# simrig_controller.net
KiCad netlist of a schematic drawn in Altium Designer
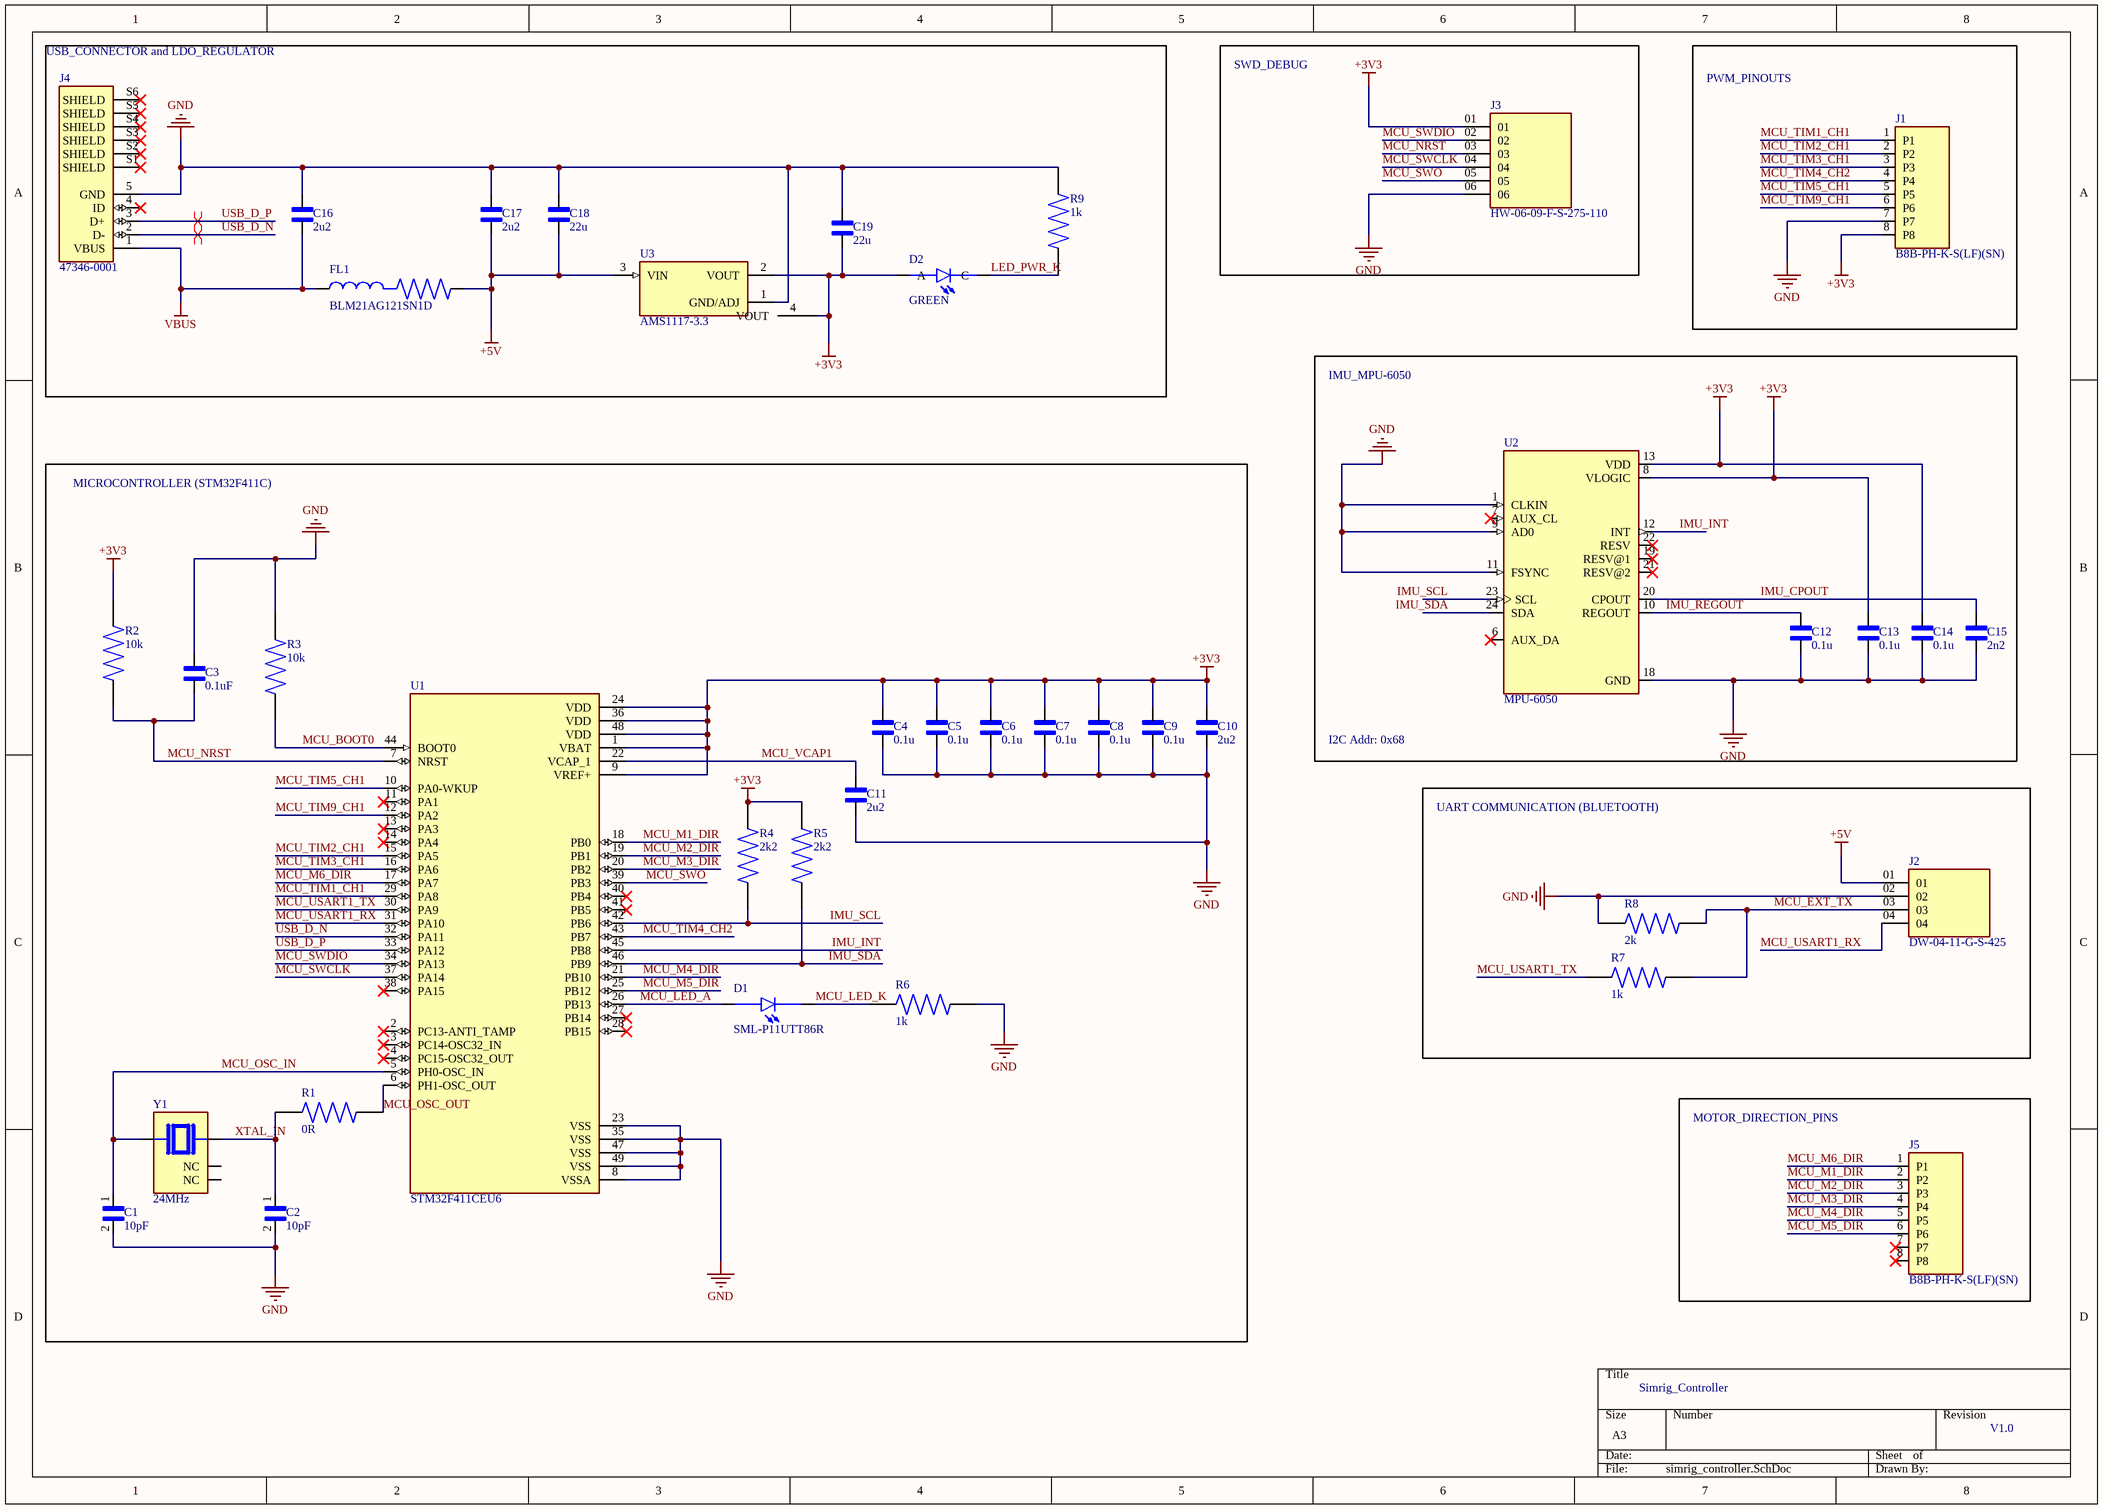
[diagram p0: simrig_controller.SchDoc]

(export (version "E")
  (design (tool "Eeschema 10.0.6"))
  (components
    (comp (ref "C1")
      (value "10pF")
      (footprint "CAPC1005X55N")
      (description "CERAMIC CAPACITOR 10PF 50V, C0G, 5%, 0402, FULL REEL")
      (fields (field (name "MF") "{'manufacturer': u'Yageo'}") (field (name "MP") "CC0402JRNPO9BN100"))
      (libsource (lib "SnapEDA_Library") (part "CC0402JRNPO9BN100"))
    )
    (comp (ref "C2")
      (value "10pF")
      (footprint "CAPC1005X55N")
      (description "CERAMIC CAPACITOR 10PF 50V, C0G, 5%, 0402, FULL REEL")
      (fields (field (name "MF") "{'manufacturer': u'Yageo'}") (field (name "MP") "CC0402JRNPO9BN100"))
      (libsource (lib "SnapEDA_Library") (part "CC0402JRNPO9BN100"))
    )
    (comp (ref "C3")
      (value "0.1uF")
      (footprint "CAPC1005X55N")
      (description "CAP CER 0.1UF 16V 10% X7R 0402")
      (fields (field (name "MF") "{'manufacturer': u'KEMET'}") (field (name "MP") "C0402C104K4RALTU"))
      (libsource (lib "SnapEDA_Library") (part "C0402C104K4RALTU"))
    )
    (comp (ref "C4")
      (value "0.1u")
      (footprint "CAPC1005X55N")
      (description "CAP CER 0.1UF 16V 10% X7R 0402")
      (fields (field (name "MF") "{'manufacturer': u'KEMET'}") (field (name "MP") "C0402C104K4RALTU"))
      (libsource (lib "SnapEDA_Library") (part "C0402C104K4RALTU"))
    )
    (comp (ref "C5")
      (value "0.1u")
      (footprint "CAPC1005X55N")
      (description "CAP CER 0.1UF 16V 10% X7R 0402")
      (fields (field (name "MF") "{'manufacturer': u'KEMET'}") (field (name "MP") "C0402C104K4RALTU"))
      (libsource (lib "SnapEDA_Library") (part "C0402C104K4RALTU"))
    )
    (comp (ref "C6")
      (value "0.1u")
      (footprint "CAPC1005X55N")
      (description "CAP CER 0.1UF 16V 10% X7R 0402")
      (fields (field (name "MF") "{'manufacturer': u'KEMET'}") (field (name "MP") "C0402C104K4RALTU"))
      (libsource (lib "SnapEDA_Library") (part "C0402C104K4RALTU"))
    )
    (comp (ref "C7")
      (value "0.1u")
      (footprint "CAPC1005X55N")
      (description "CAP CER 0.1UF 16V 10% X7R 0402")
      (fields (field (name "MF") "{'manufacturer': u'KEMET'}") (field (name "MP") "C0402C104K4RALTU"))
      (libsource (lib "SnapEDA_Library") (part "C0402C104K4RALTU"))
    )
    (comp (ref "C8")
      (value "0.1u")
      (footprint "CAPC1005X55N")
      (description "CAP CER 0.1UF 16V 10% X7R 0402")
      (fields (field (name "MF") "{'manufacturer': u'KEMET'}") (field (name "MP") "C0402C104K4RALTU"))
      (libsource (lib "SnapEDA_Library") (part "C0402C104K4RALTU"))
    )
    (comp (ref "C9")
      (value "0.1u")
      (footprint "CAPC1005X55N")
      (description "CAP CER 0.1UF 16V 10% X7R 0402")
      (fields (field (name "MF") "{'manufacturer': u'KEMET'}") (field (name "MP") "C0402C104K4RALTU"))
      (libsource (lib "SnapEDA_Library") (part "C0402C104K4RALTU"))
    )
    (comp (ref "C10")
      (value "2u2")
      (footprint "CAPC1608X90N")
      (fields (field (name "MF") "{'manufacturer': u'Murata'}") (field (name "MP") "GRM188R61E225MA12D"))
      (libsource (lib "SnapEDA_Library") (part "GRM188R61E225MA12D"))
    )
    (comp (ref "C11")
      (value "2u2")
      (footprint "CAPC1608X90N")
      (fields (field (name "MF") "{'manufacturer': u'Murata'}") (field (name "MP") "GRM188R61E225MA12D"))
      (libsource (lib "SnapEDA_Library") (part "GRM188R61E225MA12D"))
    )
    (comp (ref "C12")
      (value "0.1u")
      (footprint "CAPC1005X55N")
      (description "CAP CER 0.1UF 16V 10% X7R 0402")
      (fields (field (name "MF") "{'manufacturer': u'KEMET'}") (field (name "MP") "C0402C104K4RALTU"))
      (libsource (lib "") (part "C0402C104K4RALTU_1"))
    )
    (comp (ref "C13")
      (value "0.1u")
      (footprint "CAPC1005X55N")
      (description "CAP CER 0.1UF 16V 10% X7R 0402")
      (fields (field (name "MF") "{'manufacturer': u'KEMET'}") (field (name "MP") "C0402C104K4RALTU"))
      (libsource (lib "SnapEDA_Library") (part "C0402C104K4RALTU"))
    )
    (comp (ref "C14")
      (value "0.1u")
      (footprint "CAPC1005X55N")
      (description "CAP CER 0.1UF 16V 10% X7R 0402")
      (fields (field (name "MF") "{'manufacturer': u'KEMET'}") (field (name "MP") "C0402C104K4RALTU"))
      (libsource (lib "SnapEDA_Library") (part "C0402C104K4RALTU"))
    )
    (comp (ref "C15")
      (value "2n2")
      (footprint "CAPC1005X55N")
      (description "CAP CER 0.1UF 16V 10% X7R 0402")
      (fields (field (name "MF") "{'manufacturer': u'KEMET'}") (field (name "MP") "C0402C104K4RALTU"))
      (libsource (lib "SnapEDA_Library") (part "C0402C104K4RALTU"))
    )
    (comp (ref "C16")
      (value "2u2")
      (footprint "CAPC1608X90N")
      (fields (field (name "MF") "{'manufacturer': u'Murata'}") (field (name "MP") "GRM188R61E225MA12D"))
      (libsource (lib "SnapEDA_Library") (part "GRM188R61E225MA12D"))
    )
    (comp (ref "C17")
      (value "2u2")
      (footprint "CAPC1608X90N")
      (fields (field (name "MF") "{'manufacturer': u'Murata'}") (field (name "MP") "GRM188R61E225MA12D"))
      (libsource (lib "SnapEDA_Library") (part "GRM188R61E225MA12D"))
    )
    (comp (ref "C18")
      (value "22u")
      (footprint "CAPC2012X145N")
      (description "22ÂµF Â±20% 16V Ceramic Capacitor X6S 0805 (2012 Metric)")
      (fields (field (name "MF") "{'manufacturer': u'TDK'}") (field (name "MP") "C2012X6S1C226M125AC"))
      (libsource (lib "SnapEDA_Library") (part "C2012X6S1C226M125AC"))
    )
    (comp (ref "C19")
      (value "22u")
      (footprint "CAPC2012X145N")
      (description "22ÂµF Â±20% 16V Ceramic Capacitor X6S 0805 (2012 Metric)")
      (fields (field (name "MF") "{'manufacturer': u'TDK'}") (field (name "MP") "C2012X6S1C226M125AC"))
      (libsource (lib "SnapEDA_Library") (part "C2012X6S1C226M125AC"))
    )
    (comp (ref "D1")
      (value "SML-P11UTT86R")
      (footprint "LED_SML-P11UTT86R")
      (description "LED, PICOLED, Red, 621 nm, 1.8 V, 1 mA, 2.5 mcd")
      (fields (field (name "MF") "{'manufacturer': u'Rohm'}"))
      (libsource (lib "SnapEDA_Library") (part "SML-P11UTT86R"))
    )
    (comp (ref "D2")
      (value "GREEN")
      (footprint "LED_SML-P11UTT86R")
      (description "LED Uni-Color Green 2-Pin SMD T/R")
      (fields (field (name "MF") "{'manufacturer': u'Rohm'}") (field (name "MP") "SML-P12PTT86"))
      (libsource (lib "SnapEDA_Library") (part "SML-P12PTT86"))
    )
    (comp (ref "FL1")
      (value "BLM21AG121SN1D")
      (footprint "BEADC2012X105N")
      (fields (field (name "MF") "{'manufacturer': u'Murata'}"))
      (libsource (lib "SnapEDA_Library") (part "BLM21AG121SN1D"))
    )
    (comp (ref "J1")
      (value "B8B-PH-K-S(LF)(SN)")
      (footprint "JST_B8B-PH-K-S(LF)(SN)")
      (description "PH Series 2 mm Pitch 8 Position Through Hole Top Entry Shrouded Header")
      (fields (field (name "MF") "{'manufacturer': u'JST Sales'}"))
      (libsource (lib "SnapEDA_Library") (part "B8B-PH-K-S(LF)(SN)"))
    )
    (comp (ref "J2")
      (value "DW-04-11-G-S-425")
      (footprint "SAMTEC_DW-04-11-G-S-425")
      (fields (field (name "MF") "{'manufacturer': u'Samtec'}"))
      (libsource (lib "SnapEDA_Library") (part "DW-04-11-G-S-425"))
    )
    (comp (ref "J3")
      (value "HW-06-09-F-S-275-110")
      (footprint "SAMTEC_HW-06-09-F-S-275-110")
      (fields (field (name "MF") "{'manufacturer': u'Samtec'}"))
      (libsource (lib "SnapEDA_Library") (part "HW-06-09-F-S-275-110"))
    )
    (comp (ref "J4")
      (value "47346-0001")
      (footprint "MOLEX_47346-0001")
      (description "USB Connectors MICRO USB B RECPT BTTM MOUNT ASSY")
      (fields (field (name "MF") "{'manufacturer': u'Molex'}"))
      (libsource (lib "SnapEDA_Library") (part "47346-0001"))
    )
    (comp (ref "J5")
      (value "B8B-PH-K-S(LF)(SN)")
      (footprint "JST_B8B-PH-K-S(LF)(SN)")
      (description "PH Series 2 mm Pitch 8 Position Through Hole Top Entry Shrouded Header")
      (fields (field (name "MF") "{'manufacturer': u'JST Sales'}"))
      (libsource (lib "SnapEDA_Library") (part "B8B-PH-K-S(LF)(SN)"))
    )
    (comp (ref "R1")
      (value "0R")
      (footprint "RESC1005X37N")
      (fields (field (name "MF") "{'manufacturer': u'Vishay'}") (field (name "MP") "MCS04020D1002BE000"))
      (libsource (lib "SnapEDA_Library") (part "MCS04020D1002BE000"))
    )
    (comp (ref "R2")
      (value "10k")
      (footprint "RESC1005X37N")
      (fields (field (name "MF") "{'manufacturer': u'Vishay'}") (field (name "MP") "MCS04020D1002BE000"))
      (libsource (lib "SnapEDA_Library") (part "MCS04020D1002BE000"))
    )
    (comp (ref "R3")
      (value "10k")
      (footprint "RESC1005X37N")
      (fields (field (name "MF") "{'manufacturer': u'Vishay'}") (field (name "MP") "MCS04020D1002BE000"))
      (libsource (lib "SnapEDA_Library") (part "MCS04020D1002BE000"))
    )
    (comp (ref "R4")
      (value "2k2")
      (footprint "RESC1005X35N")
      (description "RES SMD 2.2K OHM 0.1% 1/16W 0402")
      (fields (field (name "MF") "{'manufacturer': u'Yageo'}") (field (name "MP") "RT0402BRB072K2L"))
      (libsource (lib "SnapEDA_Library") (part "RT0402BRB072K2L"))
    )
    (comp (ref "R5")
      (value "2k2")
      (footprint "RESC1005X35N")
      (description "RES SMD 2.2K OHM 0.1% 1/16W 0402")
      (fields (field (name "MF") "{'manufacturer': u'Yageo'}") (field (name "MP") "RT0402BRB072K2L"))
      (libsource (lib "SnapEDA_Library") (part "RT0402BRB072K2L"))
    )
    (comp (ref "R6")
      (value "1k")
      (footprint "RESC1005X37N")
      (fields (field (name "MF") "{'manufacturer': u'Vishay'}") (field (name "MP") "MCS04020D1002BE000"))
      (libsource (lib "SnapEDA_Library") (part "MCS04020D1002BE000"))
    )
    (comp (ref "R7")
      (value "1k")
      (footprint "RESC1005X37N")
      (fields (field (name "MF") "{'manufacturer': u'Vishay'}") (field (name "MP") "MCS04020D1002BE000"))
      (libsource (lib "SnapEDA_Library") (part "MCS04020D1002BE000"))
    )
    (comp (ref "R8")
      (value "2k")
      (footprint "RESC1005X37N")
      (fields (field (name "MF") "{'manufacturer': u'Vishay'}") (field (name "MP") "MCS04020D1002BE000"))
      (libsource (lib "SnapEDA_Library") (part "MCS04020D1002BE000"))
    )
    (comp (ref "R9")
      (value "1k")
      (footprint "RESC1005X37N")
      (fields (field (name "MF") "{'manufacturer': u'Vishay'}") (field (name "MP") "MCS04020D1002BE000"))
      (libsource (lib "SnapEDA_Library") (part "MCS04020D1002BE000"))
    )
    (comp (ref "U1")
      (value "STM32F411CEU6")
      (footprint "STM32F411CEU6:QFN50P700X700X60-49N")
      (fields (field (name "MF") "{'manufacturer': u'STMicroelectronics'}"))
      (libsource (lib "*") (part "STM32F411CEU6"))
    )
    (comp (ref "U2")
      (value "MPU-6050")
      (footprint "QFN50P400X400X95-24N")
      (description "MPU-6050 Six-Axis (Gyro + Accelerometer) MEMS MotionTrackingâ„¢ Devices")
      (fields (field (name "MF") "{'manufacturer': u'TDK InvenSense'}"))
      (libsource (lib "SnapEDA_Library") (part "MPU-6050"))
    )
    (comp (ref "U3")
      (value "AMS1117-3.3")
      (footprint "SOT229P700X180-4N")
      (fields (field (name "MF") "{'manufacturer': u'ams AG'}"))
      (libsource (lib "SnapEDA_Library") (part "AMS1117-3.3"))
    )
    (comp (ref "Y1")
      (value "24MHz")
      (footprint "XTAL_7V24000002")
      (fields (field (name "MF") "{'manufacturer': u'TXC CORPORATION'}") (field (name "MP") "7V24000002"))
      (libsource (lib "SnapEDA_Library") (part "7V24000002"))
    )
  )
  (nets
    (net (code "1") (name "+3V3") (class "Default")
      (node (ref "C10") (pin "2") (pinfunction "2_2") (pintype "passive"))
      (node (ref "C13") (pin "1") (pinfunction "1_1") (pintype "passive"))
      (node (ref "C14") (pin "1") (pinfunction "1_1") (pintype "passive"))
      (node (ref "C19") (pin "1") (pinfunction "1_1") (pintype "passive"))
      (node (ref "C4") (pin "1") (pinfunction "1_1") (pintype "passive"))
      (node (ref "C5") (pin "1") (pinfunction "1_1") (pintype "passive"))
      (node (ref "C6") (pin "1") (pinfunction "1_1") (pintype "passive"))
      (node (ref "C7") (pin "1") (pinfunction "1_1") (pintype "passive"))
      (node (ref "C8") (pin "1") (pinfunction "1_1") (pintype "passive"))
      (node (ref "C9") (pin "1") (pinfunction "1_1") (pintype "passive"))
      (node (ref "D2") (pin "A") (pinfunction "A_A") (pintype "passive"))
      (node (ref "J1") (pin "8") (pinfunction "P8_8") (pintype "passive"))
      (node (ref "J3") (pin "01") (pinfunction "01_01") (pintype "passive"))
      (node (ref "R2") (pin "1") (pinfunction "1_1") (pintype "passive"))
      (node (ref "R4") (pin "2") (pinfunction "2_2") (pintype "passive"))
      (node (ref "R5") (pin "2") (pinfunction "2_2") (pintype "passive"))
      (node (ref "U1") (pin "1") (pinfunction "VBAT_1") (pintype "power_in"))
      (node (ref "U1") (pin "24") (pinfunction "VDD_24") (pintype "power_in"))
      (node (ref "U1") (pin "36") (pinfunction "VDD_36") (pintype "power_in"))
      (node (ref "U1") (pin "48") (pinfunction "VDD_48") (pintype "power_in"))
      (node (ref "U1") (pin "9") (pinfunction "VREF+_9") (pintype "power_in"))
      (node (ref "U2") (pin "13") (pinfunction "VDD_13") (pintype "power_in"))
      (node (ref "U2") (pin "8") (pinfunction "VLOGIC_8") (pintype "power_in"))
      (node (ref "U3") (pin "2") (pinfunction "VOUT_2") (pintype "power_in"))
      (node (ref "U3") (pin "4") (pinfunction "VOUT_4") (pintype "power_in"))
    )
    (net (code "2") (name "+5V") (class "Default")
      (node (ref "C17") (pin "1") (pinfunction "1_1") (pintype "passive"))
      (node (ref "C18") (pin "1") (pinfunction "1_1") (pintype "passive"))
      (node (ref "FL1") (pin "2") (pinfunction "2_2") (pintype "passive"))
      (node (ref "J2") (pin "01") (pinfunction "01_01") (pintype "passive"))
      (node (ref "U3") (pin "3") (pinfunction "VIN_3") (pintype "input"))
    )
    (net (code "3") (name "/IMU_CPOUT") (class "Default")
      (node (ref "C15") (pin "1") (pinfunction "1_1") (pintype "passive"))
      (node (ref "U2") (pin "20") (pinfunction "CPOUT_20") (pintype "passive"))
    )
    (net (code "4") (name "/IMU_INT") (class "Default")
      (node (ref "U1") (pin "45") (pinfunction "PB8_45") (pintype "bidirectional"))
      (node (ref "U2") (pin "12") (pinfunction "INT_12") (pintype "output"))
    )
    (net (code "5") (name "/IMU_REGOUT") (class "Default")
      (node (ref "C12") (pin "2") (pinfunction "2_2") (pintype "passive"))
      (node (ref "U2") (pin "10") (pinfunction "REGOUT_10") (pintype "passive"))
    )
    (net (code "6") (name "/IMU_SCL") (class "Default")
      (node (ref "R4") (pin "1") (pinfunction "1_1") (pintype "passive"))
      (node (ref "U1") (pin "42") (pinfunction "PB6_42") (pintype "bidirectional"))
      (node (ref "U2") (pin "23") (pinfunction "SCL_23") (pintype "input"))
    )
    (net (code "7") (name "/IMU_SDA") (class "Default")
      (node (ref "R5") (pin "1") (pinfunction "1_1") (pintype "passive"))
      (node (ref "U1") (pin "46") (pinfunction "PB9_46") (pintype "bidirectional"))
      (node (ref "U2") (pin "24") (pinfunction "SDA_24") (pintype "bidirectional"))
    )
    (net (code "8") (name "/LED_PWR_K") (class "Default")
      (node (ref "D2") (pin "C") (pinfunction "C_C") (pintype "passive"))
      (node (ref "R9") (pin "1") (pinfunction "1_1") (pintype "passive"))
    )
    (net (code "9") (name "/MCU_BOOT0") (class "Default")
      (node (ref "R3") (pin "1") (pinfunction "1_1") (pintype "passive"))
      (node (ref "U1") (pin "44") (pinfunction "BOOT0_44") (pintype "input"))
    )
    (net (code "10") (name "/MCU_EXT_TX") (class "Default")
      (node (ref "J2") (pin "03") (pinfunction "03_03") (pintype "passive"))
      (node (ref "R7") (pin "1") (pinfunction "1_1") (pintype "passive"))
      (node (ref "R8") (pin "1") (pinfunction "1_1") (pintype "passive"))
    )
    (net (code "11") (name "/MCU_LED_A") (class "Default")
      (node (ref "D1") (pin "A") (pinfunction "A_A") (pintype "passive"))
      (node (ref "U1") (pin "26") (pinfunction "PB13_26") (pintype "bidirectional"))
    )
    (net (code "12") (name "/MCU_LED_K") (class "Default")
      (node (ref "D1") (pin "C") (pinfunction "C_C") (pintype "passive"))
      (node (ref "R6") (pin "2") (pinfunction "2_2") (pintype "passive"))
    )
    (net (code "13") (name "/MCU_M1_DIR") (class "Default")
      (node (ref "J5") (pin "2") (pinfunction "P2_2") (pintype "passive"))
      (node (ref "U1") (pin "18") (pinfunction "PB0_18") (pintype "bidirectional"))
    )
    (net (code "14") (name "/MCU_M2_DIR") (class "Default")
      (node (ref "J5") (pin "3") (pinfunction "P3_3") (pintype "passive"))
      (node (ref "U1") (pin "19") (pinfunction "PB1_19") (pintype "bidirectional"))
    )
    (net (code "15") (name "/MCU_M3_DIR") (class "Default")
      (node (ref "J5") (pin "4") (pinfunction "P4_4") (pintype "passive"))
      (node (ref "U1") (pin "20") (pinfunction "PB2_20") (pintype "bidirectional"))
    )
    (net (code "16") (name "/MCU_M4_DIR") (class "Default")
      (node (ref "J5") (pin "5") (pinfunction "P5_5") (pintype "passive"))
      (node (ref "U1") (pin "21") (pinfunction "PB10_21") (pintype "bidirectional"))
    )
    (net (code "17") (name "/MCU_M5_DIR") (class "Default")
      (node (ref "J5") (pin "6") (pinfunction "P6_6") (pintype "passive"))
      (node (ref "U1") (pin "25") (pinfunction "PB12_25") (pintype "bidirectional"))
    )
    (net (code "18") (name "/MCU_M6_DIR") (class "Default")
      (node (ref "J5") (pin "1") (pinfunction "P1_1") (pintype "passive"))
      (node (ref "U1") (pin "17") (pinfunction "PA7_17") (pintype "bidirectional"))
    )
    (net (code "19") (name "/MCU_NRST") (class "Default")
      (node (ref "C3") (pin "2") (pinfunction "2_2") (pintype "passive"))
      (node (ref "J3") (pin "03") (pinfunction "03_03") (pintype "passive"))
      (node (ref "R2") (pin "2") (pinfunction "2_2") (pintype "passive"))
      (node (ref "U1") (pin "7") (pinfunction "NRST_7") (pintype "bidirectional"))
    )
    (net (code "20") (name "/MCU_OSC_IN") (class "Default")
      (node (ref "C1") (pin "1") (pinfunction "1_1") (pintype "passive"))
      (node (ref "U1") (pin "5") (pinfunction "PH0-OSC_IN_5") (pintype "bidirectional"))
      (node (ref "Y1") (pin "1") (pinfunction "1_1") (pintype "passive"))
    )
    (net (code "21") (name "/MCU_OSC_OUT") (class "Default")
      (node (ref "R1") (pin "1") (pinfunction "1_1") (pintype "passive"))
      (node (ref "U1") (pin "6") (pinfunction "PH1-OSC_OUT_6") (pintype "bidirectional"))
    )
    (net (code "22") (name "/MCU_SWCLK") (class "Default")
      (node (ref "J3") (pin "04") (pinfunction "04_04") (pintype "passive"))
      (node (ref "U1") (pin "37") (pinfunction "PA14_37") (pintype "bidirectional"))
    )
    (net (code "23") (name "/MCU_SWDIO") (class "Default")
      (node (ref "J3") (pin "02") (pinfunction "02_02") (pintype "passive"))
      (node (ref "U1") (pin "34") (pinfunction "PA13_34") (pintype "bidirectional"))
    )
    (net (code "24") (name "/MCU_SWO") (class "Default")
      (node (ref "J3") (pin "05") (pinfunction "05_05") (pintype "passive"))
      (node (ref "U1") (pin "39") (pinfunction "PB3_39") (pintype "bidirectional"))
    )
    (net (code "25") (name "/MCU_TIM1_CH1") (class "Default")
      (node (ref "J1") (pin "1") (pinfunction "P1_1") (pintype "passive"))
      (node (ref "U1") (pin "29") (pinfunction "PA8_29") (pintype "bidirectional"))
    )
    (net (code "26") (name "/MCU_TIM2_CH1") (class "Default")
      (node (ref "J1") (pin "2") (pinfunction "P2_2") (pintype "passive"))
      (node (ref "U1") (pin "15") (pinfunction "PA5_15") (pintype "bidirectional"))
    )
    (net (code "27") (name "/MCU_TIM3_CH1") (class "Default")
      (node (ref "J1") (pin "3") (pinfunction "P3_3") (pintype "passive"))
      (node (ref "U1") (pin "16") (pinfunction "PA6_16") (pintype "bidirectional"))
    )
    (net (code "28") (name "/MCU_TIM4_CH2") (class "Default")
      (node (ref "J1") (pin "4") (pinfunction "P4_4") (pintype "passive"))
      (node (ref "U1") (pin "43") (pinfunction "PB7_43") (pintype "bidirectional"))
    )
    (net (code "29") (name "/MCU_TIM5_CH1") (class "Default")
      (node (ref "J1") (pin "5") (pinfunction "P5_5") (pintype "passive"))
      (node (ref "U1") (pin "10") (pinfunction "PA0-WKUP_10") (pintype "bidirectional"))
    )
    (net (code "30") (name "/MCU_TIM9_CH1") (class "Default")
      (node (ref "J1") (pin "6") (pinfunction "P6_6") (pintype "passive"))
      (node (ref "U1") (pin "12") (pinfunction "PA2_12") (pintype "bidirectional"))
    )
    (net (code "31") (name "/MCU_USART1_RX") (class "Default")
      (node (ref "J2") (pin "04") (pinfunction "04_04") (pintype "passive"))
      (node (ref "U1") (pin "31") (pinfunction "PA10_31") (pintype "bidirectional"))
    )
    (net (code "32") (name "/MCU_USART1_TX") (class "Default")
      (node (ref "R7") (pin "2") (pinfunction "2_2") (pintype "passive"))
      (node (ref "U1") (pin "30") (pinfunction "PA9_30") (pintype "bidirectional"))
    )
    (net (code "33") (name "/MCU_VCAP1") (class "Default")
      (node (ref "C11") (pin "2") (pinfunction "2_2") (pintype "passive"))
      (node (ref "U1") (pin "22") (pinfunction "VCAP_1_22") (pintype "power_in"))
    )
    (net (code "34") (name "/USB_D_N") (class "Default")
      (node (ref "J4") (pin "2") (pinfunction "D-_2") (pintype "bidirectional"))
      (node (ref "U1") (pin "32") (pinfunction "PA11_32") (pintype "bidirectional"))
    )
    (net (code "35") (name "/USB_D_P") (class "Default")
      (node (ref "J4") (pin "3") (pinfunction "D+_3") (pintype "bidirectional"))
      (node (ref "U1") (pin "33") (pinfunction "PA12_33") (pintype "bidirectional"))
    )
    (net (code "36") (name "/XTAL_IN") (class "Default")
      (node (ref "C2") (pin "1") (pinfunction "1_1") (pintype "passive"))
      (node (ref "R1") (pin "2") (pinfunction "2_2") (pintype "passive"))
      (node (ref "Y1") (pin "3") (pinfunction "2_3") (pintype "passive"))
    )
    (net (code "37") (name "GND") (class "Default")
      (node (ref "C1") (pin "2") (pinfunction "2_2") (pintype "passive"))
      (node (ref "C10") (pin "1") (pinfunction "1_1") (pintype "passive"))
      (node (ref "C11") (pin "1") (pinfunction "1_1") (pintype "passive"))
      (node (ref "C12") (pin "1") (pinfunction "1_1") (pintype "passive"))
      (node (ref "C13") (pin "2") (pinfunction "2_2") (pintype "passive"))
      (node (ref "C14") (pin "2") (pinfunction "2_2") (pintype "passive"))
      (node (ref "C15") (pin "2") (pinfunction "2_2") (pintype "passive"))
      (node (ref "C16") (pin "2") (pinfunction "2_2") (pintype "passive"))
      (node (ref "C17") (pin "2") (pinfunction "2_2") (pintype "passive"))
      (node (ref "C18") (pin "2") (pinfunction "2_2") (pintype "passive"))
      (node (ref "C19") (pin "2") (pinfunction "2_2") (pintype "passive"))
      (node (ref "C2") (pin "2") (pinfunction "2_2") (pintype "passive"))
      (node (ref "C3") (pin "1") (pinfunction "1_1") (pintype "passive"))
      (node (ref "C4") (pin "2") (pinfunction "2_2") (pintype "passive"))
      (node (ref "C5") (pin "2") (pinfunction "2_2") (pintype "passive"))
      (node (ref "C6") (pin "2") (pinfunction "2_2") (pintype "passive"))
      (node (ref "C7") (pin "2") (pinfunction "2_2") (pintype "passive"))
      (node (ref "C8") (pin "2") (pinfunction "2_2") (pintype "passive"))
      (node (ref "C9") (pin "2") (pinfunction "2_2") (pintype "passive"))
      (node (ref "J1") (pin "7") (pinfunction "P7_7") (pintype "passive"))
      (node (ref "J2") (pin "02") (pinfunction "02_02") (pintype "passive"))
      (node (ref "J3") (pin "06") (pinfunction "06_06") (pintype "passive"))
      (node (ref "J4") (pin "5") (pinfunction "GND_5") (pintype "power_in"))
      (node (ref "R3") (pin "2") (pinfunction "2_2") (pintype "passive"))
      (node (ref "R6") (pin "1") (pinfunction "1_1") (pintype "passive"))
      (node (ref "R8") (pin "2") (pinfunction "2_2") (pintype "passive"))
      (node (ref "R9") (pin "2") (pinfunction "2_2") (pintype "passive"))
      (node (ref "U1") (pin "23") (pinfunction "VSS_23") (pintype "power_in"))
      (node (ref "U1") (pin "35") (pinfunction "VSS_35") (pintype "power_in"))
      (node (ref "U1") (pin "47") (pinfunction "VSS_47") (pintype "power_in"))
      (node (ref "U1") (pin "49") (pinfunction "VSS_49") (pintype "power_in"))
      (node (ref "U1") (pin "8") (pinfunction "VSSA_8") (pintype "power_in"))
      (node (ref "U2") (pin "1") (pinfunction "CLKIN_1") (pintype "input"))
      (node (ref "U2") (pin "11") (pinfunction "FSYNC_11") (pintype "input"))
      (node (ref "U2") (pin "18") (pinfunction "GND_18") (pintype "power_in"))
      (node (ref "U2") (pin "9") (pinfunction "AD0_9") (pintype "input"))
      (node (ref "U3") (pin "1") (pinfunction "GND/ADJ_1") (pintype "power_in"))
    )
    (net (code "38") (name "VBUS") (class "Default")
      (node (ref "C16") (pin "1") (pinfunction "1_1") (pintype "passive"))
      (node (ref "FL1") (pin "1") (pinfunction "1_1") (pintype "passive"))
      (node (ref "J4") (pin "1") (pinfunction "VBUS_1") (pintype "power_in"))
    )
    (net (code "39") (name "unconnected-(J4-ID-Pad4)") (class "Default")
      (node (ref "J4") (pin "4") (pinfunction "ID_4") (pintype "bidirectional+no_connect"))
    )
    (net (code "40") (name "unconnected-(J4-SHIELD-PadS1)") (class "Default")
      (node (ref "J4") (pin "S1") (pinfunction "SHIELD_S1") (pintype "passive+no_connect"))
    )
    (net (code "41") (name "unconnected-(J4-SHIELD-PadS2)") (class "Default")
      (node (ref "J4") (pin "S2") (pinfunction "SHIELD_S2") (pintype "passive+no_connect"))
    )
    (net (code "42") (name "unconnected-(J4-SHIELD-PadS3)") (class "Default")
      (node (ref "J4") (pin "S3") (pinfunction "SHIELD_S3") (pintype "passive+no_connect"))
    )
    (net (code "43") (name "unconnected-(J4-SHIELD-PadS4)") (class "Default")
      (node (ref "J4") (pin "S4") (pinfunction "SHIELD_S4") (pintype "passive+no_connect"))
    )
    (net (code "44") (name "unconnected-(J4-SHIELD-PadS5)") (class "Default")
      (node (ref "J4") (pin "S5") (pinfunction "SHIELD_S5") (pintype "passive+no_connect"))
    )
    (net (code "45") (name "unconnected-(J4-SHIELD-PadS6)") (class "Default")
      (node (ref "J4") (pin "S6") (pinfunction "SHIELD_S6") (pintype "passive+no_connect"))
    )
    (net (code "46") (name "unconnected-(J5-P7-Pad7)") (class "Default")
      (node (ref "J5") (pin "7") (pinfunction "P7_7") (pintype "passive+no_connect"))
    )
    (net (code "47") (name "unconnected-(J5-P8-Pad8)") (class "Default")
      (node (ref "J5") (pin "8") (pinfunction "P8_8") (pintype "passive+no_connect"))
    )
    (net (code "48") (name "unconnected-(U1-PA1-Pad11)") (class "Default")
      (node (ref "U1") (pin "11") (pinfunction "PA1_11") (pintype "bidirectional+no_connect"))
    )
    (net (code "49") (name "unconnected-(U1-PA3-Pad13)") (class "Default")
      (node (ref "U1") (pin "13") (pinfunction "PA3_13") (pintype "bidirectional+no_connect"))
    )
    (net (code "50") (name "unconnected-(U1-PA4-Pad14)") (class "Default")
      (node (ref "U1") (pin "14") (pinfunction "PA4_14") (pintype "bidirectional+no_connect"))
    )
    (net (code "51") (name "unconnected-(U1-PA15-Pad38)") (class "Default")
      (node (ref "U1") (pin "38") (pinfunction "PA15_38") (pintype "bidirectional+no_connect"))
    )
    (net (code "52") (name "unconnected-(U1-PB4-Pad40)") (class "Default")
      (node (ref "U1") (pin "40") (pinfunction "PB4_40") (pintype "bidirectional+no_connect"))
    )
    (net (code "53") (name "unconnected-(U1-PB5-Pad41)") (class "Default")
      (node (ref "U1") (pin "41") (pinfunction "PB5_41") (pintype "bidirectional+no_connect"))
    )
    (net (code "54") (name "unconnected-(U1-PB14-Pad27)") (class "Default")
      (node (ref "U1") (pin "27") (pinfunction "PB14_27") (pintype "bidirectional+no_connect"))
    )
    (net (code "55") (name "unconnected-(U1-PB15-Pad28)") (class "Default")
      (node (ref "U1") (pin "28") (pinfunction "PB15_28") (pintype "bidirectional+no_connect"))
    )
    (net (code "56") (name "unconnected-(U1-PC13-ANTI_TAMP-Pad2)") (class "Default")
      (node (ref "U1") (pin "2") (pinfunction "PC13-ANTI_TAMP_2") (pintype "bidirectional+no_connect"))
    )
    (net (code "57") (name "unconnected-(U1-PC14-OSC32_IN-Pad3)") (class "Default")
      (node (ref "U1") (pin "3") (pinfunction "PC14-OSC32_IN_3") (pintype "bidirectional+no_connect"))
    )
    (net (code "58") (name "unconnected-(U1-PC15-OSC32_OUT-Pad4)") (class "Default")
      (node (ref "U1") (pin "4") (pinfunction "PC15-OSC32_OUT_4") (pintype "bidirectional+no_connect"))
    )
    (net (code "59") (name "unconnected-(U2-AUX_CL-Pad7)") (class "Default")
      (node (ref "U2") (pin "7") (pinfunction "AUX_CL_7") (pintype "input+no_connect"))
    )
    (net (code "60") (name "unconnected-(U2-AUX_DA-Pad6)") (class "Default")
      (node (ref "U2") (pin "6") (pinfunction "AUX_DA_6") (pintype "bidirectional+no_connect"))
    )
    (net (code "61") (name "unconnected-(U2-RESV-Pad22)") (class "Default")
      (node (ref "U2") (pin "22") (pinfunction "RESV_22") (pintype "passive+no_connect"))
    )
    (net (code "62") (name "unconnected-(U2-RESV@1-Pad19)") (class "Default")
      (node (ref "U2") (pin "19") (pinfunction "RESV@1_19") (pintype "passive+no_connect"))
    )
    (net (code "63") (name "unconnected-(U2-RESV@2-Pad21)") (class "Default")
      (node (ref "U2") (pin "21") (pinfunction "RESV@2_21") (pintype "passive+no_connect"))
    )
    (net (code "64") (name "unconnected-(Y1-NC-Pad2)") (class "Default")
      (node (ref "Y1") (pin "2") (pinfunction "NC_2") (pintype "passive"))
    )
    (net (code "65") (name "unconnected-(Y1-NC-Pad4)") (class "Default")
      (node (ref "Y1") (pin "4") (pinfunction "NC_4") (pintype "passive"))
    )
  )
)
